# STM8.net
KiCad netlist of a schematic drawn in Altium Designer
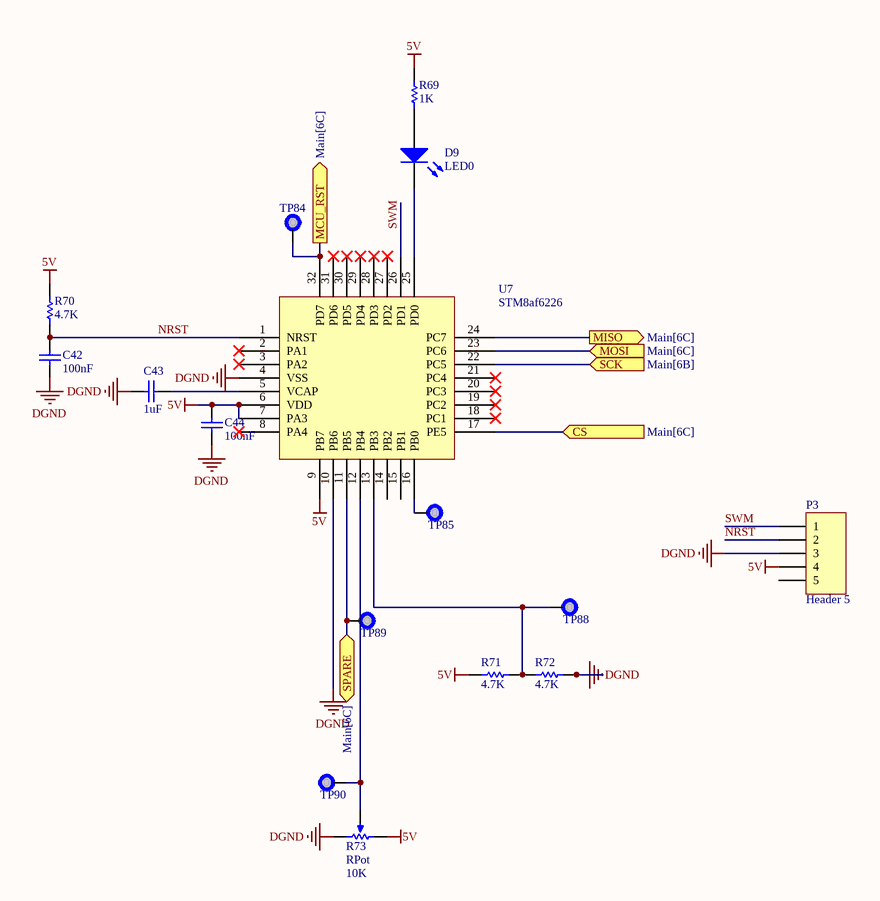
[diagram p0: STM8.SchDoc]

(export (version "E")
  (design (tool "Eeschema 10.0.6"))
  (components
    (comp (ref "C42")
      (value "100nF")
      (footprint "0603C")
      (description "Capacitor")
      (fields (field (name "Comment") "CGA3E2X7R1H104K080AA") (field (name "PUBLISHER") "Altium Limited"))
      (libsource (lib "Miscellaneous Devices") (part "Cap"))
    )
    (comp (ref "C43")
      (value "1uF")
      (footprint "0603C")
      (description "Capacitor")
      (fields (field (name "Comment") "CGA3E2X7R1H104K080AA") (field (name "PUBLISHER") "Altium Limited"))
      (libsource (lib "Miscellaneous Devices") (part "Cap"))
    )
    (comp (ref "C44")
      (value "100nF")
      (footprint "0603C")
      (description "Capacitor")
      (fields (field (name "Comment") "CGA3E2X7R1H104K080AA") (field (name "PUBLISHER") "Altium Limited"))
      (libsource (lib "Miscellaneous Devices") (part "Cap"))
    )
    (comp (ref "D9")
      (value "LED0")
      (footprint "0805LED")
      (description "Typical INFRARED GaAs LED")
      (fields (field (name "PUBLISHER") "Altium Limited"))
      (libsource (lib "Miscellaneous Devices") (part "LED0"))
    )
    (comp (ref "P3")
      (value "Header 5")
      (footprint "HDR1X5")
      (description "Header, 5-Pin")
      (fields (field (name "PUBLISHER") "Altium Limited"))
      (libsource (lib "Miscellaneous Connectors") (part "Header 5"))
    )
    (comp (ref "R69")
      (value "1K")
      (footprint "0805")
      (description "Resistor")
      (fields (field (name "Comment") "Res1") (field (name "PUBLISHER") "Altium Limited"))
      (libsource (lib "Miscellaneous Devices") (part "Res1"))
    )
    (comp (ref "R70")
      (value "4.7K")
      (footprint "0805")
      (description "Resistor")
      (fields (field (name "Comment") "Res1") (field (name "PUBLISHER") "Altium Limited"))
      (libsource (lib "Miscellaneous Devices") (part "Res1"))
    )
    (comp (ref "R71")
      (value "4.7K")
      (footprint "0805")
      (description "Resistor")
      (fields (field (name "Comment") "Res1") (field (name "PUBLISHER") "Altium Limited"))
      (libsource (lib "Miscellaneous Devices") (part "Res1"))
    )
    (comp (ref "R72")
      (value "4.7K")
      (footprint "0805")
      (description "Resistor")
      (fields (field (name "Comment") "Res1") (field (name "PUBLISHER") "Altium Limited"))
      (libsource (lib "Miscellaneous Devices") (part "Res1"))
    )
    (comp (ref "R73")
      (value "RPot")
      (footprint "POT-MULTITURN")
      (description "Potentiometer")
      (fields (field (name "ALTIUM_VALUE") "10K") (field (name "PUBLISHER") "Altium Limited"))
      (libsource (lib "Miscellaneous Devices") (part "RPot"))
    )
    (comp (ref "TP84") (value "TestPoint") (footprint "TP") (libsource (lib "SchlibV0.1") (part "TestPoint")))
    (comp (ref "TP85") (value "TestPoint") (footprint "TP") (libsource (lib "SchlibV0.1") (part "TestPoint")))
    (comp (ref "TP88") (value "TestPoint") (footprint "TP") (libsource (lib "SchlibV0.1") (part "TestPoint")))
    (comp (ref "TP89") (value "TestPoint") (footprint "TP") (libsource (lib "SchlibV0.1") (part "TestPoint")))
    (comp (ref "TP90") (value "TestPoint") (footprint "TP") (libsource (lib "SchlibV0.1") (part "TestPoint")))
    (comp (ref "U7")
      (value "STM8af6226")
      (footprint "LQFP-32")
      (libsource (lib "SchlibV0.1") (part "STM8af6226"))
    )
  )
  (nets
    (net (code "1") (name "/CS") (class "Default")
      (node (ref "U7") (pin "17") (pinfunction "PE5_17") (pintype "passive"))
    )
    (net (code "2") (name "/MCU_RST") (class "Default")
      (node (ref "TP84") (pin "1") (pintype "passive"))
      (node (ref "U7") (pin "32") (pinfunction "PD7_32") (pintype "passive"))
    )
    (net (code "3") (name "/MISO") (class "Default")
      (node (ref "U7") (pin "24") (pinfunction "PC7_24") (pintype "passive"))
    )
    (net (code "4") (name "/MOSI") (class "Default")
      (node (ref "U7") (pin "23") (pinfunction "PC6_23") (pintype "passive"))
    )
    (net (code "5") (name "/NRST") (class "Default")
      (node (ref "C42") (pin "2") (pinfunction "2_2") (pintype "passive"))
      (node (ref "P3") (pin "2") (pinfunction "2_2") (pintype "passive"))
      (node (ref "R70") (pin "2") (pinfunction "2_2") (pintype "passive"))
      (node (ref "U7") (pin "1") (pinfunction "NRST_1") (pintype "passive"))
    )
    (net (code "6") (name "/SCK") (class "Default")
      (node (ref "U7") (pin "22") (pinfunction "PC5_22") (pintype "passive"))
    )
    (net (code "7") (name "/SPARE") (class "Default")
      (node (ref "TP89") (pin "1") (pintype "passive"))
      (node (ref "U7") (pin "11") (pinfunction "PB5_11") (pintype "passive"))
    )
    (net (code "8") (name "/SWM") (class "Default")
      (node (ref "P3") (pin "1") (pinfunction "1_1") (pintype "passive"))
      (node (ref "U7") (pin "26") (pinfunction "PD1_26") (pintype "passive"))
    )
    (net (code "9") (name "5V") (class "Default")
      (node (ref "C44") (pin "1") (pinfunction "1_1") (pintype "passive"))
      (node (ref "P3") (pin "4") (pinfunction "4_4") (pintype "passive"))
      (node (ref "R69") (pin "2") (pinfunction "2_2") (pintype "passive"))
      (node (ref "R70") (pin "1") (pinfunction "1_1") (pintype "passive"))
      (node (ref "R71") (pin "2") (pinfunction "2_2") (pintype "passive"))
      (node (ref "R73") (pin "1") (pinfunction "TOP_1") (pintype "passive"))
      (node (ref "U7") (pin "6") (pinfunction "VDD_6") (pintype "passive"))
      (node (ref "U7") (pin "7") (pinfunction "PA3_7") (pintype "passive"))
      (node (ref "U7") (pin "9") (pinfunction "PB7_9") (pintype "passive"))
    )
    (net (code "10") (name "DGND") (class "Default")
      (node (ref "C42") (pin "1") (pinfunction "1_1") (pintype "passive"))
      (node (ref "C43") (pin "2") (pinfunction "2_2") (pintype "passive"))
      (node (ref "C44") (pin "2") (pinfunction "2_2") (pintype "passive"))
      (node (ref "P3") (pin "3") (pinfunction "3_3") (pintype "passive"))
      (node (ref "R72") (pin "1") (pinfunction "1_1") (pintype "passive"))
      (node (ref "R73") (pin "3") (pinfunction "BOT_3") (pintype "passive"))
      (node (ref "U7") (pin "10") (pinfunction "PB6_10") (pintype "passive"))
      (node (ref "U7") (pin "4") (pinfunction "VSS_4") (pintype "passive"))
    )
    (net (code "11") (name "Net-(D9-A)") (class "Default")
      (node (ref "D9") (pin "1") (pinfunction "A_1") (pintype "passive"))
      (node (ref "R69") (pin "1") (pinfunction "1_1") (pintype "passive"))
    )
    (net (code "12") (name "Net-(D9-K)") (class "Default")
      (node (ref "D9") (pin "2") (pinfunction "K_2") (pintype "passive"))
      (node (ref "U7") (pin "25") (pinfunction "PD0_25") (pintype "passive"))
    )
    (net (code "13") (name "Net-(R73-TAP)") (class "Default")
      (node (ref "R73") (pin "2") (pinfunction "TAP_2") (pintype "passive"))
      (node (ref "TP90") (pin "1") (pintype "passive"))
      (node (ref "U7") (pin "12") (pinfunction "PB4_12") (pintype "passive"))
    )
    (net (code "14") (name "Net-(U7-PB0)") (class "Default")
      (node (ref "TP85") (pin "1") (pintype "passive"))
      (node (ref "U7") (pin "16") (pinfunction "PB0_16") (pintype "passive"))
    )
    (net (code "15") (name "Net-(U7-PB3)") (class "Default")
      (node (ref "R71") (pin "1") (pinfunction "1_1") (pintype "passive"))
      (node (ref "R72") (pin "2") (pinfunction "2_2") (pintype "passive"))
      (node (ref "TP88") (pin "1") (pintype "passive"))
      (node (ref "U7") (pin "13") (pinfunction "PB3_13") (pintype "passive"))
    )
    (net (code "16") (name "Net-(U7-VCAP)") (class "Default")
      (node (ref "C43") (pin "1") (pinfunction "1_1") (pintype "passive"))
      (node (ref "U7") (pin "5") (pinfunction "VCAP_5") (pintype "passive"))
    )
    (net (code "17") (name "unconnected-(P3-Pad5)") (class "Default")
      (node (ref "P3") (pin "5") (pinfunction "5_5") (pintype "passive"))
    )
    (net (code "18") (name "unconnected-(U7-PA1-Pad2)") (class "Default")
      (node (ref "U7") (pin "2") (pinfunction "PA1_2") (pintype "passive+no_connect"))
    )
    (net (code "19") (name "unconnected-(U7-PA2-Pad3)") (class "Default")
      (node (ref "U7") (pin "3") (pinfunction "PA2_3") (pintype "passive+no_connect"))
    )
    (net (code "20") (name "unconnected-(U7-PA4-Pad8)") (class "Default")
      (node (ref "U7") (pin "8") (pinfunction "PA4_8") (pintype "passive+no_connect"))
    )
    (net (code "21") (name "unconnected-(U7-PB1-Pad15)") (class "Default")
      (node (ref "U7") (pin "15") (pinfunction "PB1_15") (pintype "passive"))
    )
    (net (code "22") (name "unconnected-(U7-PB2-Pad14)") (class "Default")
      (node (ref "U7") (pin "14") (pinfunction "PB2_14") (pintype "passive"))
    )
    (net (code "23") (name "unconnected-(U7-PC1-Pad18)") (class "Default")
      (node (ref "U7") (pin "18") (pinfunction "PC1_18") (pintype "passive+no_connect"))
    )
    (net (code "24") (name "unconnected-(U7-PC2-Pad19)") (class "Default")
      (node (ref "U7") (pin "19") (pinfunction "PC2_19") (pintype "passive+no_connect"))
    )
    (net (code "25") (name "unconnected-(U7-PC3-Pad20)") (class "Default")
      (node (ref "U7") (pin "20") (pinfunction "PC3_20") (pintype "passive+no_connect"))
    )
    (net (code "26") (name "unconnected-(U7-PC4-Pad21)") (class "Default")
      (node (ref "U7") (pin "21") (pinfunction "PC4_21") (pintype "passive+no_connect"))
    )
    (net (code "27") (name "unconnected-(U7-PD2-Pad27)") (class "Default")
      (node (ref "U7") (pin "27") (pinfunction "PD2_27") (pintype "passive+no_connect"))
    )
    (net (code "28") (name "unconnected-(U7-PD3-Pad28)") (class "Default")
      (node (ref "U7") (pin "28") (pinfunction "PD3_28") (pintype "passive+no_connect"))
    )
    (net (code "29") (name "unconnected-(U7-PD4-Pad29)") (class "Default")
      (node (ref "U7") (pin "29") (pinfunction "PD4_29") (pintype "passive+no_connect"))
    )
    (net (code "30") (name "unconnected-(U7-PD5-Pad30)") (class "Default")
      (node (ref "U7") (pin "30") (pinfunction "PD5_30") (pintype "passive+no_connect"))
    )
    (net (code "31") (name "unconnected-(U7-PD6-Pad31)") (class "Default")
      (node (ref "U7") (pin "31") (pinfunction "PD6_31") (pintype "passive+no_connect"))
    )
  )
)
